# Sheet_2_-_Moteurs.net
KiCad netlist of a schematic drawn in Altium Designer
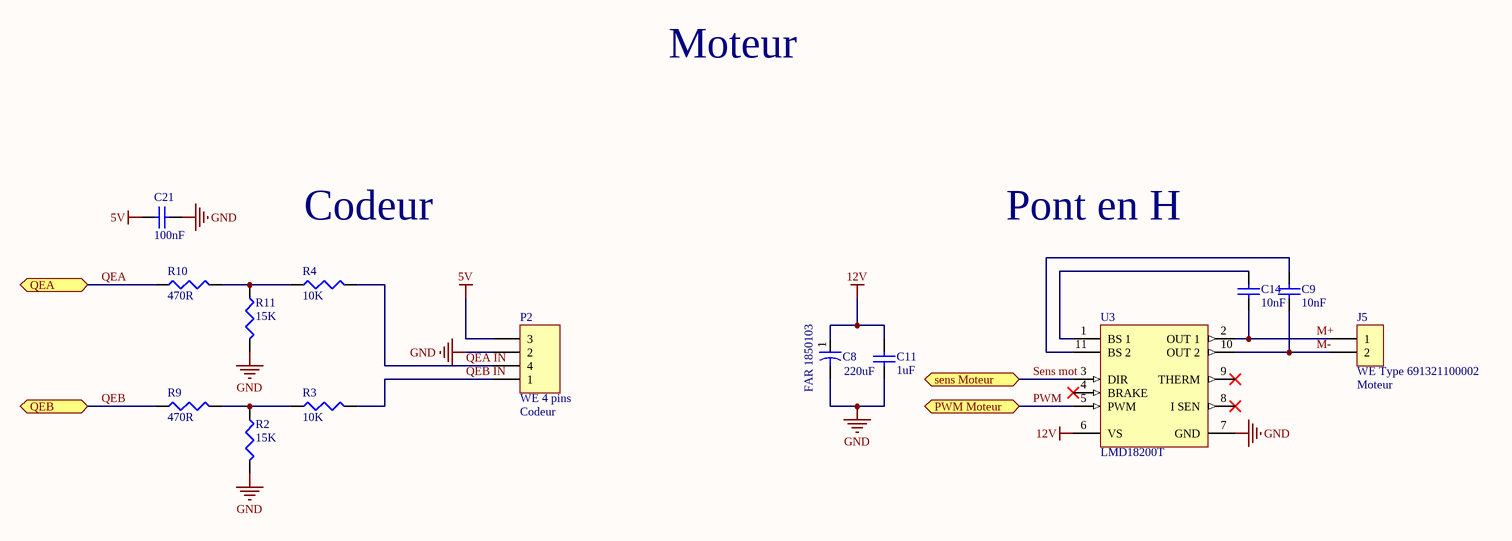
[diagram p0: Sheet 2 - Moteurs.SchDoc]

(export (version "E")
  (design (tool "Eeschema 10.0.6"))
  (components
    (comp (ref "C8")
      (value "220uF")
      (footprint "Capa CMS D6.3_E1.8")
      (description "EEEFK1C221XP")
      (fields (field (name "RÉFERENCE COMMANDE") "FAR 1850103") (field (name "PUBLISHER") "Altium Limited"))
      (libsource (lib "Miscellaneous Devices") (part "Cap2"))
    )
    (comp (ref "C9")
      (value "10nF")
      (footprint "pcb_peb_1:C0805")
      (description "Capacitor 0805")
      (fields (field (name "PUBLISHER") "Altium Limited"))
      (libsource (lib "Miscellaneous Devices") (part "Cap"))
    )
    (comp (ref "C11")
      (value "1uF")
      (footprint "pcb_peb_1:C0805")
      (description "Capacitor 0805")
      (fields (field (name "PUBLISHER") "Altium Limited"))
      (libsource (lib "Miscellaneous Devices") (part "Cap"))
    )
    (comp (ref "C14")
      (value "10nF")
      (footprint "pcb_peb_1:C0805")
      (description "Capacitor 0805")
      (fields (field (name "PUBLISHER") "Altium Limited"))
      (libsource (lib "Miscellaneous Devices") (part "Cap"))
    )
    (comp (ref "C21")
      (value "100nF")
      (footprint "pcb_peb_1:C0805")
      (description "Capacitor 0805")
      (fields (field (name "PUBLISHER") "Altium Limited"))
      (libsource (lib "Miscellaneous Devices") (part "Cap"))
    )
    (comp (ref "J5")
      (value "WE Type 691321100002")
      (footprint "691321100002")
      (description "WR-TBL Terminal block - serie 3211 - 3.50 mm")
      (fields
        (field (name "MANUFACTURER") "Würth Elektronik eiSos GmbH")
        (field (name "VALUE1") "Moteur")
        (field (name "CREATED BY") "Karrer Zheng")
      )
      (libsource (lib "6913211000xx") (part "WE-Terminal Blocks Plugable Type 691321100002"))
    )
    (comp (ref "P2")
      (value "WE 4 pins")
      (footprint "690367280476")
      (description "Header, 4-Pin")
      (fields (field (name "VALUE1") "Codeur") (field (name "PUBLISHER") "Altium Limited"))
      (libsource (lib "Miscellaneous Connectors") (part "MHDR1X4"))
    )
    (comp (ref "R2")
      (value "15K")
      (footprint "0805")
      (description "Resistor 0805")
      (fields (field (name "PUBLISHER") "Altium Limited"))
      (libsource (lib "Miscellaneous Devices") (part "Res3"))
    )
    (comp (ref "R3")
      (value "10K")
      (footprint "0805")
      (description "Resistor 0805")
      (fields (field (name "PUBLISHER") "Altium Limited"))
      (libsource (lib "Miscellaneous Devices") (part "Res3"))
    )
    (comp (ref "R4")
      (value "10K")
      (footprint "0805")
      (description "Resistor 0805")
      (fields (field (name "PUBLISHER") "Altium Limited"))
      (libsource (lib "Miscellaneous Devices") (part "Res3"))
    )
    (comp (ref "R9")
      (value "470R")
      (footprint "0805")
      (description "Resistor 0805")
      (fields (field (name "PUBLISHER") "Altium Limited"))
      (libsource (lib "Miscellaneous Devices") (part "Res3"))
    )
    (comp (ref "R10")
      (value "470R")
      (footprint "0805")
      (description "Resistor 0805")
      (fields (field (name "PUBLISHER") "Altium Limited"))
      (libsource (lib "Miscellaneous Devices") (part "Res3"))
    )
    (comp (ref "R11")
      (value "15K")
      (footprint "0805")
      (description "Resistor 0805")
      (fields (field (name "PUBLISHER") "Altium Limited"))
      (libsource (lib "Miscellaneous Devices") (part "Res3"))
    )
    (comp (ref "U3")
      (value "LMD18200T")
      (footprint "TA11B")
      (description "3A, 55V H-Bridge")
      (fields
        (field (name "MANUFACTURER") "National Semiconductor")
        (field (name "DIGIKEYPARTNUMBER") "LMD18200T-ND")
        (field (name "PUBLISHER") "Altium Limited")
      )
      (libsource (lib "NSC MiscPower") (part "LMD18200T"))
    )
  )
  (nets
    (net (code "1") (name "/M+") (class "Default")
      (node (ref "C14") (pin "2") (pinfunction "2_2") (pintype "passive"))
      (node (ref "J5") (pin "1") (pinfunction "1_1") (pintype "passive"))
      (node (ref "U3") (pin "2") (pinfunction "OUT_1_2") (pintype "output"))
    )
    (net (code "2") (name "/M-") (class "Default")
      (node (ref "C9") (pin "2") (pinfunction "2_2") (pintype "passive"))
      (node (ref "J5") (pin "2") (pinfunction "2_2") (pintype "passive"))
      (node (ref "U3") (pin "10") (pinfunction "OUT_2_10") (pintype "output"))
    )
    (net (code "3") (name "/PWM") (class "Default")
      (node (ref "U3") (pin "5") (pinfunction "PWM_5") (pintype "input"))
    )
    (net (code "4") (name "/QEA") (class "Default")
      (node (ref "R10") (pin "1") (pinfunction "1_1") (pintype "passive"))
    )
    (net (code "5") (name "/QEA IN") (class "Default")
      (node (ref "P2") (pin "4") (pinfunction "4_4") (pintype "passive"))
      (node (ref "R4") (pin "2") (pinfunction "2_2") (pintype "passive"))
    )
    (net (code "6") (name "/QEB") (class "Default")
      (node (ref "R9") (pin "1") (pinfunction "1_1") (pintype "passive"))
    )
    (net (code "7") (name "/QEB IN") (class "Default")
      (node (ref "P2") (pin "1") (pinfunction "1_1") (pintype "passive"))
      (node (ref "R3") (pin "2") (pinfunction "2_2") (pintype "passive"))
    )
    (net (code "8") (name "/Sens mot") (class "Default")
      (node (ref "U3") (pin "3") (pinfunction "DIR_3") (pintype "input"))
    )
    (net (code "9") (name "5V") (class "Default")
      (node (ref "C21") (pin "2") (pinfunction "2_2") (pintype "passive"))
      (node (ref "P2") (pin "3") (pinfunction "3_3") (pintype "passive"))
    )
    (net (code "10") (name "12V") (class "Default")
      (node (ref "C11") (pin "2") (pinfunction "2_2") (pintype "passive"))
      (node (ref "C8") (pin "1") (pinfunction "1_1") (pintype "passive"))
      (node (ref "U3") (pin "6") (pinfunction "VS_6") (pintype "power_in"))
    )
    (net (code "11") (name "GND") (class "Default")
      (node (ref "C11") (pin "1") (pinfunction "1_1") (pintype "passive"))
      (node (ref "C21") (pin "1") (pinfunction "1_1") (pintype "passive"))
      (node (ref "C8") (pin "2") (pinfunction "2_2") (pintype "passive"))
      (node (ref "P2") (pin "2") (pinfunction "2_2") (pintype "passive"))
      (node (ref "R11") (pin "2") (pinfunction "2_2") (pintype "passive"))
      (node (ref "R2") (pin "2") (pinfunction "2_2") (pintype "passive"))
      (node (ref "U3") (pin "7") (pinfunction "GND_7") (pintype "power_in"))
    )
    (net (code "12") (name "Net-(R2-Pad1)") (class "Default")
      (node (ref "R2") (pin "1") (pinfunction "1_1") (pintype "passive"))
      (node (ref "R3") (pin "1") (pinfunction "1_1") (pintype "passive"))
      (node (ref "R9") (pin "2") (pinfunction "2_2") (pintype "passive"))
    )
    (net (code "13") (name "Net-(R10-Pad2)") (class "Default")
      (node (ref "R10") (pin "2") (pinfunction "2_2") (pintype "passive"))
      (node (ref "R11") (pin "1") (pinfunction "1_1") (pintype "passive"))
      (node (ref "R4") (pin "1") (pinfunction "1_1") (pintype "passive"))
    )
    (net (code "14") (name "Net-(U3-BS_1)") (class "Default")
      (node (ref "C14") (pin "1") (pinfunction "1_1") (pintype "passive"))
      (node (ref "U3") (pin "1") (pinfunction "BS_1_1") (pintype "passive"))
    )
    (net (code "15") (name "Net-(U3-BS_2)") (class "Default")
      (node (ref "C9") (pin "1") (pinfunction "1_1") (pintype "passive"))
      (node (ref "U3") (pin "11") (pinfunction "BS_2_11") (pintype "passive"))
    )
    (net (code "16") (name "unconnected-(U3-BRAKE-Pad4)") (class "Default")
      (node (ref "U3") (pin "4") (pinfunction "BRAKE_4") (pintype "input+no_connect"))
    )
    (net (code "17") (name "unconnected-(U3-I_SEN-Pad8)") (class "Default")
      (node (ref "U3") (pin "8") (pinfunction "I_SEN_8") (pintype "output+no_connect"))
    )
    (net (code "18") (name "unconnected-(U3-THERM-Pad9)") (class "Default")
      (node (ref "U3") (pin "9") (pinfunction "THERM_9") (pintype "output+no_connect"))
    )
  )
)
